# Overview_and_Power.net
KiCad netlist of a schematic drawn in Altium Designer
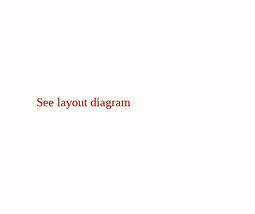
[diagram p0: Overview and Power.SchDoc, left]
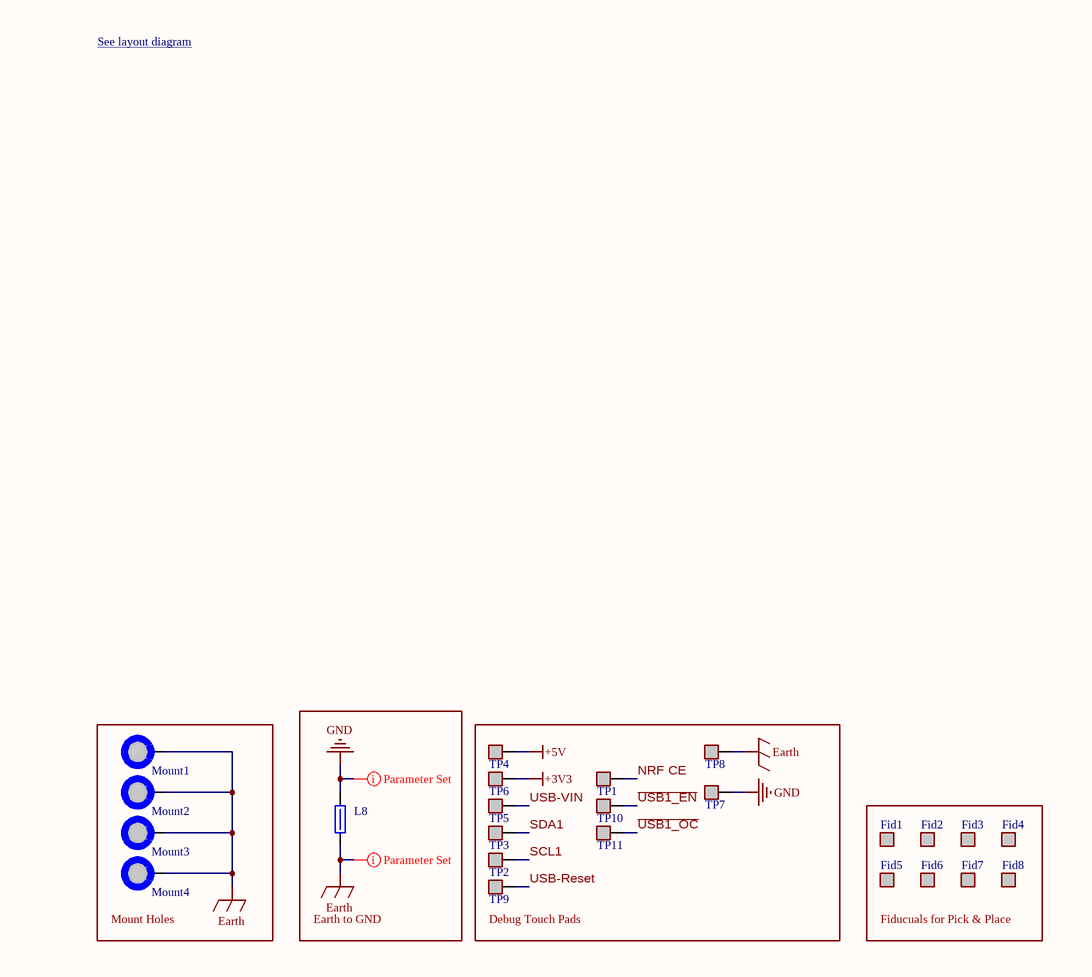
[diagram p1: Overview and Power.SchDoc, right]

(export (version "E")
  (design (tool "Eeschema 10.0.6"))
  (components
    (comp (ref "Fid1")
      (value "JLCPCB Pick & Place Fiducial")
      (footprint "[Fiducial] JLCPCB Pick & Place")
      (libsource (lib "RADM Connectors") (part "[Fiducial] JLCPCB Pick & Place"))
    )
    (comp (ref "Fid2")
      (value "JLCPCB Pick & Place Fiducial")
      (footprint "[Fiducial] JLCPCB Pick & Place")
      (libsource (lib "RADM Connectors") (part "[Fiducial] JLCPCB Pick & Place"))
    )
    (comp (ref "Fid3")
      (value "JLCPCB Pick & Place Fiducial")
      (footprint "[Fiducial] JLCPCB Pick & Place")
      (libsource (lib "RADM Connectors") (part "[Fiducial] JLCPCB Pick & Place"))
    )
    (comp (ref "Fid4")
      (value "JLCPCB Pick & Place Fiducial")
      (footprint "[Fiducial] JLCPCB Pick & Place")
      (libsource (lib "RADM Connectors") (part "[Fiducial] JLCPCB Pick & Place"))
    )
    (comp (ref "Fid5")
      (value "JLCPCB Pick & Place Fiducial")
      (footprint "[Fiducial] JLCPCB Pick & Place")
      (libsource (lib "RADM Connectors") (part "[Fiducial] JLCPCB Pick & Place"))
    )
    (comp (ref "Fid6")
      (value "JLCPCB Pick & Place Fiducial")
      (footprint "[Fiducial] JLCPCB Pick & Place")
      (libsource (lib "RADM Connectors") (part "[Fiducial] JLCPCB Pick & Place"))
    )
    (comp (ref "Fid7")
      (value "JLCPCB Pick & Place Fiducial")
      (footprint "[Fiducial] JLCPCB Pick & Place")
      (libsource (lib "RADM Connectors") (part "[Fiducial] JLCPCB Pick & Place"))
    )
    (comp (ref "Fid8")
      (value "JLCPCB Pick & Place Fiducial")
      (footprint "[Fiducial] JLCPCB Pick & Place")
      (libsource (lib "RADM Connectors") (part "[Fiducial] JLCPCB Pick & Place"))
    )
    (comp (ref "L8")
      (value "742792040")
      (footprint "[Ferrite] SMD Bead 0805 (2)")
      (libsource (lib "RADM Components") (part "[Ferrite] SMD Ferrite Bead (2)"))
    )
    (comp (ref "Mount1")
      (value "M3 Mount Hole")
      (footprint "[Mount] M3 Mount Hole")
      (description "Place at least 4.5mm from board edge. Plated.")
      (libsource (lib "RADM Connectors") (part "[Mount] M3 Mount Hole"))
    )
    (comp (ref "Mount2")
      (value "M3 Mount Hole")
      (footprint "[Mount] M3 Mount Hole")
      (description "Place at least 4.5mm from board edge. Plated.")
      (libsource (lib "RADM Connectors") (part "[Mount] M3 Mount Hole"))
    )
    (comp (ref "Mount3")
      (value "M3 Mount Hole")
      (footprint "[Mount] M3 Mount Hole")
      (description "Place at least 4.5mm from board edge. Plated.")
      (libsource (lib "RADM Connectors") (part "[Mount] M3 Mount Hole"))
    )
    (comp (ref "Mount4")
      (value "M3 Mount Hole")
      (footprint "[Mount] M3 Mount Hole")
      (description "Place at least 4.5mm from board edge. Plated.")
      (libsource (lib "RADM Connectors") (part "[Mount] M3 Mount Hole"))
    )
    (comp (ref "TP1")
      (value "Probe Pad")
      (footprint "[Probe] Touch Pad")
      (libsource (lib "RADM Connectors") (part "[Probe] Touch Pad"))
    )
    (comp (ref "TP2")
      (value "Probe Pad")
      (footprint "[Probe] Touch Pad")
      (libsource (lib "RADM Connectors") (part "[Probe] Touch Pad"))
    )
    (comp (ref "TP3")
      (value "Probe Pad")
      (footprint "[Probe] Touch Pad")
      (libsource (lib "RADM Connectors") (part "[Probe] Touch Pad"))
    )
    (comp (ref "TP4")
      (value "Probe Pad")
      (footprint "[Probe] Touch Pad")
      (libsource (lib "RADM Connectors") (part "[Probe] Touch Pad"))
    )
    (comp (ref "TP5")
      (value "Probe Pad")
      (footprint "[Probe] Touch Pad")
      (libsource (lib "RADM Connectors") (part "[Probe] Touch Pad"))
    )
    (comp (ref "TP6")
      (value "Probe Pad")
      (footprint "[Probe] Touch Pad")
      (libsource (lib "RADM Connectors") (part "[Probe] Touch Pad"))
    )
    (comp (ref "TP7")
      (value "Probe Pad")
      (footprint "[Probe] Touch Pad")
      (libsource (lib "RADM Connectors") (part "[Probe] Touch Pad"))
    )
    (comp (ref "TP8")
      (value "Probe Pad")
      (footprint "[Probe] Touch Pad")
      (libsource (lib "RADM Connectors") (part "[Probe] Touch Pad"))
    )
    (comp (ref "TP9")
      (value "Probe Pad")
      (footprint "[Probe] Touch Pad")
      (libsource (lib "RADM Connectors") (part "[Probe] Touch Pad"))
    )
    (comp (ref "TP10")
      (value "Probe Pad")
      (footprint "[Probe] Touch Pad")
      (libsource (lib "RADM Connectors") (part "[Probe] Touch Pad"))
    )
    (comp (ref "TP11")
      (value "Probe Pad")
      (footprint "[Probe] Touch Pad")
      (libsource (lib "RADM Connectors") (part "[Probe] Touch Pad"))
    )
  )
  (nets
    (net (code "1") (name "+3V3") (class "Default")
      (node (ref "TP6") (pin "1") (pinfunction "1_1") (pintype "passive"))
    )
    (net (code "2") (name "+5V") (class "Default")
      (node (ref "TP4") (pin "1") (pinfunction "1_1") (pintype "passive"))
    )
    (net (code "3") (name "/NRF CE") (class "Default")
      (node (ref "TP1") (pin "1") (pinfunction "1_1") (pintype "passive"))
    )
    (net (code "4") (name "/SCL1") (class "Default")
      (node (ref "TP2") (pin "1") (pinfunction "1_1") (pintype "passive"))
    )
    (net (code "5") (name "/SDA1") (class "Default")
      (node (ref "TP3") (pin "1") (pinfunction "1_1") (pintype "passive"))
    )
    (net (code "6") (name "/USB-Reset") (class "Default")
      (node (ref "TP9") (pin "1") (pinfunction "1_1") (pintype "passive"))
    )
    (net (code "7") (name "/USB-VIN") (class "Default")
      (node (ref "TP5") (pin "1") (pinfunction "1_1") (pintype "passive"))
    )
    (net (code "8") (name "/USB1_EN") (class "Default")
      (node (ref "TP10") (pin "1") (pinfunction "1_1") (pintype "passive"))
    )
    (net (code "9") (name "/USB1_OC") (class "Default")
      (node (ref "TP11") (pin "1") (pinfunction "1_1") (pintype "passive"))
    )
    (net (code "10") (name "Earth") (class "Default")
      (node (ref "L8") (pin "1") (pinfunction "1_1") (pintype "passive"))
      (node (ref "Mount1") (pin "1") (pintype "power_in"))
      (node (ref "Mount2") (pin "1") (pintype "power_in"))
      (node (ref "Mount3") (pin "1") (pintype "power_in"))
      (node (ref "Mount4") (pin "1") (pintype "power_in"))
      (node (ref "TP8") (pin "1") (pinfunction "1_1") (pintype "passive"))
    )
    (net (code "11") (name "GND") (class "Default")
      (node (ref "L8") (pin "2") (pinfunction "2_2") (pintype "passive"))
      (node (ref "TP7") (pin "1") (pinfunction "1_1") (pintype "passive"))
    )
  )
)
